# ADC.net
KiCad netlist of a schematic drawn in Altium Designer
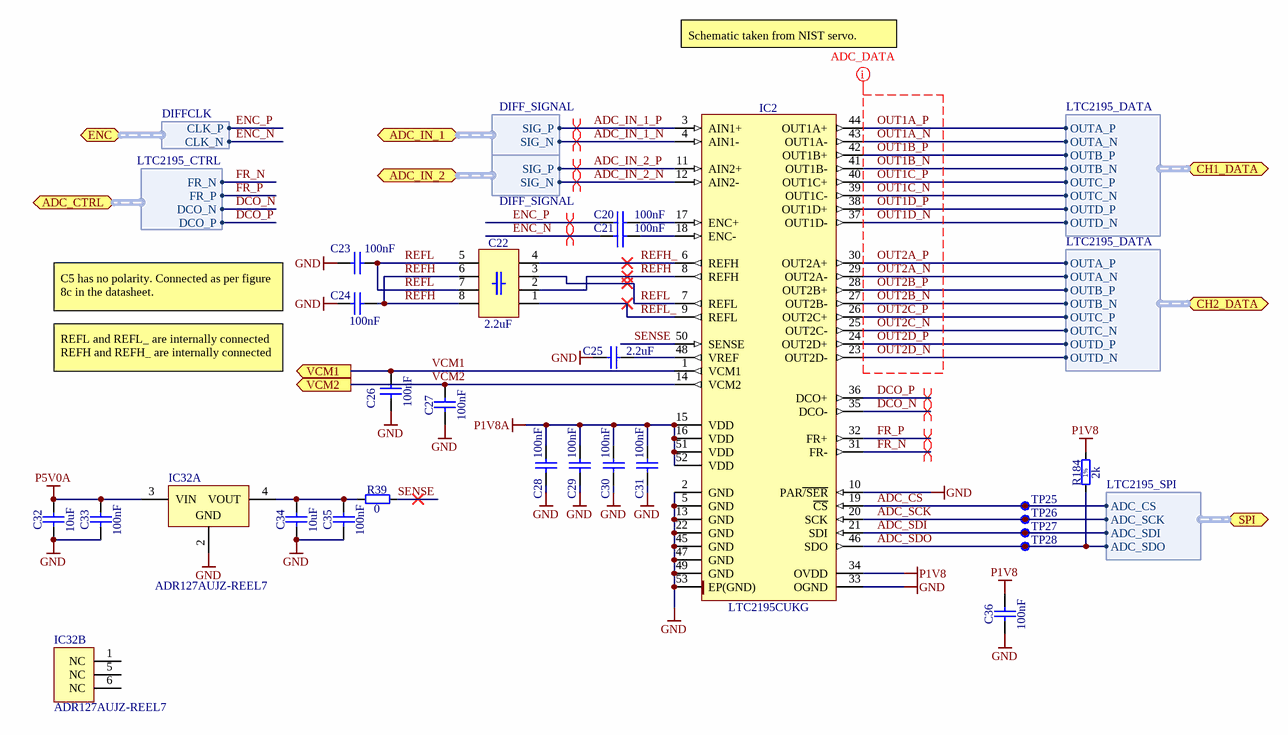
[diagram p0: ADC.SchDoc]

(export (version "E")
  (design (tool "Eeschema 10.0.6"))
  (components
    (comp (ref "C20")
      (value "100nF")
      (footprint "CAPC1005X55N")
      (description "Non-polarised capacitor")
      (fields
        (field (name "PART NUMBER") "CC0402_100NF_16V_10%_X5R")
        (field (name "VOLTAGE") "16V")
        (field (name "AUTHOR") "CERN DEM JLC")
      )
      (libsource (lib "Capacitors") (part "Capacitor - non polarized"))
    )
    (comp (ref "C21")
      (value "100nF")
      (footprint "CAPC1005X55N")
      (description "Non-polarised capacitor")
      (fields
        (field (name "PART NUMBER") "CC0402_100NF_16V_10%_X5R")
        (field (name "VOLTAGE") "16V")
        (field (name "AUTHOR") "CERN DEM JLC")
      )
      (libsource (lib "Capacitors") (part "Capacitor - non polarized"))
    )
    (comp (ref "C22")
      (value "2.2uF")
      (footprint "CAPCAF50P125X200X95-8N")
      (description "8 Terminals Low ESL Chip Multilayer Ceramic Capacitors for General Purpose")
      (fields
        (field (name "PART NUMBER") "CC0508_2.2UF_4V_20%_X7S_MURATA_LLA219C70G225M")
        (field (name "VOLTAGE") "4V")
        (field (name "AUTHOR") "CERN DEM BC")
      )
      (libsource (lib "Capacitors") (part "Capacitor MURATA LLA"))
    )
    (comp (ref "C23")
      (value "100nF")
      (footprint "CAPC1005X55N")
      (description "Non-polarised capacitor")
      (fields
        (field (name "PART NUMBER") "CC0402_100NF_16V_10%_X5R")
        (field (name "VOLTAGE") "16V")
        (field (name "AUTHOR") "CERN DEM JLC")
      )
      (libsource (lib "Capacitors") (part "Capacitor - non polarized"))
    )
    (comp (ref "C24")
      (value "100nF")
      (footprint "CAPC1005X55N")
      (description "Non-polarised capacitor")
      (fields
        (field (name "PART NUMBER") "CC0402_100NF_16V_10%_X5R")
        (field (name "VOLTAGE") "16V")
        (field (name "AUTHOR") "CERN DEM JLC")
      )
      (libsource (lib "Capacitors") (part "Capacitor - non polarized"))
    )
    (comp (ref "C25")
      (value "2.2uF")
      (footprint "CAPC2012X140N")
      (description "Non-polarised capacitor")
      (fields
        (field (name "PART NUMBER") "CC0805_2.2UF_50V_10%_X7R")
        (field (name "VOLTAGE") "50V")
        (field (name "AUTHOR") "CERN DEM JLC")
      )
      (libsource (lib "Capacitors") (part "Capacitor - non polarized"))
    )
    (comp (ref "C26")
      (value "100nF")
      (footprint "CAPC1005X55N")
      (description "Non-polarised capacitor")
      (fields
        (field (name "PART NUMBER") "CC0402_100NF_16V_10%_X5R")
        (field (name "VOLTAGE") "16V")
        (field (name "AUTHOR") "CERN DEM JLC")
      )
      (libsource (lib "Capacitors") (part "Capacitor - non polarized"))
    )
    (comp (ref "C27")
      (value "100nF")
      (footprint "CAPC1005X55N")
      (description "Non-polarised capacitor")
      (fields
        (field (name "PART NUMBER") "CC0402_100NF_16V_10%_X5R")
        (field (name "VOLTAGE") "16V")
        (field (name "AUTHOR") "CERN DEM JLC")
      )
      (libsource (lib "Capacitors") (part "Capacitor - non polarized"))
    )
    (comp (ref "C28")
      (value "100nF")
      (footprint "CAPC1005X55N")
      (description "Non-polarised capacitor")
      (fields
        (field (name "PART NUMBER") "CC0402_100NF_16V_10%_X5R")
        (field (name "VOLTAGE") "16V")
        (field (name "AUTHOR") "CERN DEM JLC")
      )
      (libsource (lib "Capacitors") (part "Capacitor - non polarized"))
    )
    (comp (ref "C29")
      (value "100nF")
      (footprint "CAPC1005X55N")
      (description "Non-polarised capacitor")
      (fields
        (field (name "PART NUMBER") "CC0402_100NF_16V_10%_X5R")
        (field (name "VOLTAGE") "16V")
        (field (name "AUTHOR") "CERN DEM JLC")
      )
      (libsource (lib "Capacitors") (part "Capacitor - non polarized"))
    )
    (comp (ref "C30")
      (value "100nF")
      (footprint "CAPC1005X55N")
      (description "Non-polarised capacitor")
      (fields
        (field (name "PART NUMBER") "CC0402_100NF_16V_10%_X5R")
        (field (name "VOLTAGE") "16V")
        (field (name "AUTHOR") "CERN DEM JLC")
      )
      (libsource (lib "Capacitors") (part "Capacitor - non polarized"))
    )
    (comp (ref "C31")
      (value "100nF")
      (footprint "CAPC1005X55N")
      (description "Non-polarised capacitor")
      (fields
        (field (name "PART NUMBER") "CC0402_100NF_16V_10%_X5R")
        (field (name "VOLTAGE") "16V")
        (field (name "AUTHOR") "CERN DEM JLC")
      )
      (libsource (lib "Capacitors") (part "Capacitor - non polarized"))
    )
    (comp (ref "C32")
      (value "10uF")
      (footprint "CAPC1608X80N")
      (description "Non-polarised capacitor")
      (fields
        (field (name "PART NUMBER") "CC0603_10UF_10V_10%_X5R")
        (field (name "VOLTAGE") "10V")
        (field (name "AUTHOR") "CERN DEM JLC")
      )
      (libsource (lib "Capacitors") (part "Capacitor - non polarized"))
    )
    (comp (ref "C33")
      (value "100nF")
      (footprint "CAPC1005X55N")
      (description "Non-polarised capacitor")
      (fields
        (field (name "PART NUMBER") "CC0402_100NF_16V_10%_X5R")
        (field (name "VOLTAGE") "16V")
        (field (name "AUTHOR") "CERN DEM JLC")
      )
      (libsource (lib "Capacitors") (part "Capacitor - non polarized"))
    )
    (comp (ref "C34")
      (value "10uF")
      (footprint "CAPC1608X80N")
      (description "Non-polarised capacitor")
      (fields
        (field (name "PART NUMBER") "CC0603_10UF_10V_10%_X5R")
        (field (name "VOLTAGE") "10V")
        (field (name "AUTHOR") "CERN DEM JLC")
      )
      (libsource (lib "Capacitors") (part "Capacitor - non polarized"))
    )
    (comp (ref "C35")
      (value "100nF")
      (footprint "CAPC1005X55N")
      (description "Non-polarised capacitor")
      (fields
        (field (name "PART NUMBER") "CC0402_100NF_16V_10%_X5R")
        (field (name "VOLTAGE") "16V")
        (field (name "AUTHOR") "CERN DEM JLC")
      )
      (libsource (lib "Capacitors") (part "Capacitor - non polarized"))
    )
    (comp (ref "C36")
      (value "100nF")
      (footprint "CAPC1005X55N")
      (description "Non-polarised capacitor")
      (fields
        (field (name "PART NUMBER") "CC0402_100NF_16V_10%_X5R")
        (field (name "VOLTAGE") "16V")
        (field (name "AUTHOR") "CERN DEM JLC")
      )
      (libsource (lib "Capacitors") (part "Capacitor - non polarized"))
    )
    (comp (ref "IC2")
      (value "LTC2195CUKG")
      (footprint "QFN50P700X800X80-53N-R655X550")
      (description "16-Bit, 125Msps Low Power Dual ADCs")
      (fields (field (name "MANUFACTURER") "ANALOG DEVICES") (field (name "AUTHOR") "CERN DEM BC"))
      (libsource (lib "ICs And Semiconductors") (part "LTC2195"))
    )
    (comp (ref "IC32")
      (value "ADR127AUJZ-REEL7")
      (footprint "ADI-UJ-6_M")
      (fields (field (name "MANUFACTURER") "Analog Devices"))
      (libsource (lib "Altium Content Vault") (part "ADI-ADR12X-UJ-6"))
    )
    (comp (ref "R39")
      (value "0")
      (footprint "RESC1005X40N")
      (description "Resistor")
      (fields
        (field (name "PART NUMBER") "R0402_0R_JUMPER")
        (field (name "MANUFACTURER") "GENERIC")
        (field (name "AUTHOR") "CERN DEM JLC")
      )
      (libsource (lib "Resistors") (part "Resistor"))
    )
    (comp (ref "R184")
      (value "2k")
      (footprint "RESC1005X40N")
      (description "Resistor - 1%")
      (fields
        (field (name "PART NUMBER") "R0402_2K_1%_0.0625W_100PPM")
        (field (name "MANUFACTURER") "GENERIC")
        (field (name "AUTHOR") "CERN DEM JLC")
      )
      (libsource (lib "Resistors") (part "Resistor - 1%"))
    )
    (comp (ref "TP25")
      (value "SMD Pad")
      (footprint "C100")
      (description "Through Hole Pad")
      (fields (field (name "PART NUMBER") "SMD_PAD_D1MM") (field (name "AUTHOR") "CERN DEM JLC"))
      (libsource (lib "Eletro-mechanical") (part "Single SMD Pad (Round)"))
    )
    (comp (ref "TP26")
      (value "SMD Pad")
      (footprint "C100")
      (description "Through Hole Pad")
      (fields (field (name "PART NUMBER") "SMD_PAD_D1MM") (field (name "AUTHOR") "CERN DEM JLC"))
      (libsource (lib "Eletro-mechanical") (part "Single SMD Pad (Round)"))
    )
    (comp (ref "TP27")
      (value "SMD Pad")
      (footprint "C100")
      (description "Through Hole Pad")
      (fields (field (name "PART NUMBER") "SMD_PAD_D1MM") (field (name "AUTHOR") "CERN DEM JLC"))
      (libsource (lib "Eletro-mechanical") (part "Single SMD Pad (Round)"))
    )
    (comp (ref "TP28")
      (value "SMD Pad")
      (footprint "C100")
      (description "Through Hole Pad")
      (fields (field (name "PART NUMBER") "SMD_PAD_D1MM") (field (name "AUTHOR") "CERN DEM JLC"))
      (libsource (lib "Eletro-mechanical") (part "Single SMD Pad (Round)"))
    )
  )
  (nets
    (net (code "6") (name "/ADC_CS") (class "Default")
      (node (ref "IC2") (pin "19") (pinfunction "CS_19") (pintype "input"))
      (node (ref "TP25") (pin "1") (pinfunction "1_1") (pintype "bidirectional"))
    )
    (net (code "7") (name "/ADC_IN_1_N") (class "Default")
      (node (ref "IC2") (pin "4") (pinfunction "AIN1-_4") (pintype "input"))
    )
    (net (code "8") (name "/ADC_IN_1_P") (class "Default")
      (node (ref "IC2") (pin "3") (pinfunction "AIN1+_3") (pintype "input"))
    )
    (net (code "9") (name "/ADC_IN_2_N") (class "Default")
      (node (ref "IC2") (pin "12") (pinfunction "AIN2-_12") (pintype "input"))
    )
    (net (code "10") (name "/ADC_IN_2_P") (class "Default")
      (node (ref "IC2") (pin "11") (pinfunction "AIN2+_11") (pintype "input"))
    )
    (net (code "11") (name "/ADC_SCK") (class "Default")
      (node (ref "IC2") (pin "20") (pinfunction "SCK_20") (pintype "input"))
      (node (ref "TP26") (pin "1") (pinfunction "1_1") (pintype "bidirectional"))
    )
    (net (code "12") (name "/ADC_SDI") (class "Default")
      (node (ref "IC2") (pin "21") (pinfunction "SDI_21") (pintype "input"))
      (node (ref "TP27") (pin "1") (pinfunction "1_1") (pintype "bidirectional"))
    )
    (net (code "13") (name "/ADC_SDO") (class "Default")
      (node (ref "IC2") (pin "46") (pinfunction "SDO_46") (pintype "output"))
      (node (ref "R184") (pin "1") (pinfunction "1_1") (pintype "passive"))
      (node (ref "TP28") (pin "1") (pinfunction "1_1") (pintype "bidirectional"))
    )
    (net (code "14") (name "/DCO_N") (class "Default")
      (node (ref "IC2") (pin "35") (pinfunction "DCO-_35") (pintype "output"))
    )
    (net (code "15") (name "/DCO_P") (class "Default")
      (node (ref "IC2") (pin "36") (pinfunction "DCO+_36") (pintype "output"))
    )
    (net (code "16") (name "/ENC_N") (class "Default")
      (node (ref "C21") (pin "2") (pinfunction "2_2") (pintype "passive"))
    )
    (net (code "17") (name "/ENC_P") (class "Default")
      (node (ref "C20") (pin "2") (pinfunction "2_2") (pintype "passive"))
    )
    (net (code "18") (name "/FR_N") (class "Default")
      (node (ref "IC2") (pin "31") (pinfunction "FR-_31") (pintype "output"))
    )
    (net (code "19") (name "/FR_P") (class "Default")
      (node (ref "IC2") (pin "32") (pinfunction "FR+_32") (pintype "output"))
    )
    (net (code "20") (name "/OUT1A_N") (class "Default")
      (node (ref "IC2") (pin "43") (pinfunction "OUT1A-_43") (pintype "output"))
    )
    (net (code "21") (name "/OUT1A_P") (class "Default")
      (node (ref "IC2") (pin "44") (pinfunction "OUT1A+_44") (pintype "output"))
    )
    (net (code "22") (name "/OUT1B_N") (class "Default")
      (node (ref "IC2") (pin "41") (pinfunction "OUT1B-_41") (pintype "output"))
    )
    (net (code "23") (name "/OUT1B_P") (class "Default")
      (node (ref "IC2") (pin "42") (pinfunction "OUT1B+_42") (pintype "output"))
    )
    (net (code "24") (name "/OUT1C_N") (class "Default")
      (node (ref "IC2") (pin "39") (pinfunction "OUT1C-_39") (pintype "output"))
    )
    (net (code "25") (name "/OUT1C_P") (class "Default")
      (node (ref "IC2") (pin "40") (pinfunction "OUT1C+_40") (pintype "output"))
    )
    (net (code "26") (name "/OUT1D_N") (class "Default")
      (node (ref "IC2") (pin "37") (pinfunction "OUT1D-_37") (pintype "output"))
    )
    (net (code "27") (name "/OUT1D_P") (class "Default")
      (node (ref "IC2") (pin "38") (pinfunction "OUT1D+_38") (pintype "output"))
    )
    (net (code "28") (name "/OUT2A_N") (class "Default")
      (node (ref "IC2") (pin "29") (pinfunction "OUT2A-_29") (pintype "output"))
    )
    (net (code "29") (name "/OUT2A_P") (class "Default")
      (node (ref "IC2") (pin "30") (pinfunction "OUT2A+_30") (pintype "output"))
    )
    (net (code "30") (name "/OUT2B_N") (class "Default")
      (node (ref "IC2") (pin "27") (pinfunction "OUT2B-_27") (pintype "output"))
    )
    (net (code "31") (name "/OUT2B_P") (class "Default")
      (node (ref "IC2") (pin "28") (pinfunction "OUT2B+_28") (pintype "output"))
    )
    (net (code "32") (name "/OUT2C_N") (class "Default")
      (node (ref "IC2") (pin "25") (pinfunction "OUT2C-_25") (pintype "output"))
    )
    (net (code "33") (name "/OUT2C_P") (class "Default")
      (node (ref "IC2") (pin "26") (pinfunction "OUT2C+_26") (pintype "output"))
    )
    (net (code "34") (name "/OUT2D_N") (class "Default")
      (node (ref "IC2") (pin "23") (pinfunction "OUT2D-_23") (pintype "output"))
    )
    (net (code "35") (name "/OUT2D_P") (class "Default")
      (node (ref "IC2") (pin "24") (pinfunction "OUT2D+_24") (pintype "output"))
    )
    (net (code "36") (name "/REFH") (class "Default")
      (node (ref "C22") (pin "2") (pinfunction "2_2") (pintype "passive"))
      (node (ref "C22") (pin "6") (pinfunction "6_6") (pintype "passive"))
      (node (ref "C22") (pin "8") (pinfunction "8_8") (pintype "passive"))
      (node (ref "C24") (pin "1") (pinfunction "1_1") (pintype "passive"))
      (node (ref "IC2") (pin "8") (pinfunction "REFH_8") (pintype "output"))
    )
    (net (code "37") (name "/REFH_") (class "Default")
      (node (ref "C22") (pin "4") (pinfunction "4_4") (pintype "passive"))
      (node (ref "IC2") (pin "6") (pinfunction "REFH_6") (pintype "output"))
    )
    (net (code "38") (name "/REFL") (class "Default")
      (node (ref "C22") (pin "3") (pinfunction "3_3") (pintype "passive"))
      (node (ref "C22") (pin "5") (pinfunction "5_5") (pintype "passive"))
      (node (ref "C22") (pin "7") (pinfunction "7_7") (pintype "passive"))
      (node (ref "C23") (pin "1") (pinfunction "1_1") (pintype "passive"))
      (node (ref "IC2") (pin "7") (pinfunction "REFL_7") (pintype "output"))
    )
    (net (code "39") (name "/REFL_") (class "Default")
      (node (ref "C22") (pin "1") (pinfunction "1_1") (pintype "passive"))
      (node (ref "IC2") (pin "9") (pinfunction "REFL_9") (pintype "output"))
    )
    (net (code "40") (name "/SENSE") (class "Default")
      (node (ref "IC2") (pin "50") (pinfunction "SENSE_50") (pintype "input"))
      (node (ref "R39") (pin "2") (pinfunction "2_2") (pintype "passive"))
    )
    (net (code "41") (name "/VCM1") (class "Default")
      (node (ref "C26") (pin "2") (pinfunction "2_2") (pintype "passive"))
      (node (ref "IC2") (pin "1") (pinfunction "VCM1_1") (pintype "output"))
    )
    (net (code "42") (name "/VCM2") (class "Default")
      (node (ref "C27") (pin "2") (pinfunction "2_2") (pintype "passive"))
      (node (ref "IC2") (pin "14") (pinfunction "VCM2_14") (pintype "output"))
    )
    (net (code "48") (name "GND") (class "Default")
      (node (ref "C23") (pin "2") (pinfunction "2_2") (pintype "passive"))
      (node (ref "C24") (pin "2") (pinfunction "2_2") (pintype "passive"))
      (node (ref "C25") (pin "1") (pinfunction "1_1") (pintype "passive"))
      (node (ref "C26") (pin "1") (pinfunction "1_1") (pintype "passive"))
      (node (ref "C27") (pin "1") (pinfunction "1_1") (pintype "passive"))
      (node (ref "C28") (pin "2") (pinfunction "2_2") (pintype "passive"))
      (node (ref "C29") (pin "2") (pinfunction "2_2") (pintype "passive"))
      (node (ref "C30") (pin "2") (pinfunction "2_2") (pintype "passive"))
      (node (ref "C31") (pin "2") (pinfunction "2_2") (pintype "passive"))
      (node (ref "C32") (pin "1") (pinfunction "1_1") (pintype "passive"))
      (node (ref "C33") (pin "1") (pinfunction "1_1") (pintype "passive"))
      (node (ref "C34") (pin "1") (pinfunction "1_1") (pintype "passive"))
      (node (ref "C35") (pin "1") (pinfunction "1_1") (pintype "passive"))
      (node (ref "C36") (pin "1") (pinfunction "1_1") (pintype "passive"))
      (node (ref "IC2") (pin "10") (pinfunction "PAR~{/SER}_10") (pintype "input"))
      (node (ref "IC2") (pin "13") (pinfunction "GND_13") (pintype "power_in"))
      (node (ref "IC2") (pin "2") (pinfunction "GND_2") (pintype "power_in"))
      (node (ref "IC2") (pin "22") (pinfunction "GND_22") (pintype "power_in"))
      (node (ref "IC2") (pin "33") (pinfunction "OGND_33") (pintype "power_in"))
      (node (ref "IC2") (pin "45") (pinfunction "GND_45") (pintype "power_in"))
      (node (ref "IC2") (pin "47") (pinfunction "GND_47") (pintype "power_in"))
      (node (ref "IC2") (pin "49") (pinfunction "GND_49") (pintype "power_in"))
      (node (ref "IC2") (pin "5") (pinfunction "GND_5") (pintype "power_in"))
      (node (ref "IC2") (pin "53") (pinfunction "EP(GND)_53") (pintype "power_in"))
      (node (ref "IC32") (pin "2") (pinfunction "GND_2") (pintype "power_in"))
    )
    (net (code "49") (name "Net-(IC2-ENC+)") (class "Default")
      (node (ref "C20") (pin "1") (pinfunction "1_1") (pintype "passive"))
      (node (ref "IC2") (pin "17") (pinfunction "ENC+_17") (pintype "input"))
    )
    (net (code "50") (name "Net-(IC2-ENC-)") (class "Default")
      (node (ref "C21") (pin "1") (pinfunction "1_1") (pintype "passive"))
      (node (ref "IC2") (pin "18") (pinfunction "ENC-_18") (pintype "input"))
    )
    (net (code "51") (name "Net-(IC2-VREF)") (class "Default")
      (node (ref "C25") (pin "2") (pinfunction "2_2") (pintype "passive"))
      (node (ref "IC2") (pin "48") (pinfunction "VREF_48") (pintype "output"))
    )
    (net (code "52") (name "Net-(IC32A-VOUT)") (class "Default")
      (node (ref "C34") (pin "2") (pinfunction "2_2") (pintype "passive"))
      (node (ref "C35") (pin "2") (pinfunction "2_2") (pintype "passive"))
      (node (ref "IC32") (pin "4") (pinfunction "VOUT_4") (pintype "power_in"))
      (node (ref "R39") (pin "1") (pinfunction "1_1") (pintype "passive"))
    )
    (net (code "53") (name "P1V8") (class "Default")
      (node (ref "C36") (pin "2") (pinfunction "2_2") (pintype "passive"))
      (node (ref "IC2") (pin "34") (pinfunction "OVDD_34") (pintype "power_in"))
      (node (ref "R184") (pin "2") (pinfunction "2_2") (pintype "passive"))
    )
    (net (code "54") (name "P1V8A") (class "Default")
      (node (ref "C28") (pin "1") (pinfunction "1_1") (pintype "passive"))
      (node (ref "C29") (pin "1") (pinfunction "1_1") (pintype "passive"))
      (node (ref "C30") (pin "1") (pinfunction "1_1") (pintype "passive"))
      (node (ref "C31") (pin "1") (pinfunction "1_1") (pintype "passive"))
      (node (ref "IC2") (pin "15") (pinfunction "VDD_15") (pintype "power_in"))
      (node (ref "IC2") (pin "16") (pinfunction "VDD_16") (pintype "power_in"))
      (node (ref "IC2") (pin "51") (pinfunction "VDD_51") (pintype "power_in"))
      (node (ref "IC2") (pin "52") (pinfunction "VDD_52") (pintype "power_in"))
    )
    (net (code "55") (name "P5V0A") (class "Default")
      (node (ref "C32") (pin "2") (pinfunction "2_2") (pintype "passive"))
      (node (ref "C33") (pin "2") (pinfunction "2_2") (pintype "passive"))
      (node (ref "IC32") (pin "3") (pinfunction "VIN_3") (pintype "power_in"))
    )
    (net (code "56") (name "unconnected-(IC32B-NC-Pad1)") (class "Default")
      (node (ref "IC32") (pin "1") (pinfunction "NC_1") (pintype "passive"))
    )
    (net (code "57") (name "unconnected-(IC32B-NC-Pad5)") (class "Default")
      (node (ref "IC32") (pin "5") (pinfunction "NC_5") (pintype "passive"))
    )
    (net (code "58") (name "unconnected-(IC32B-NC-Pad6)") (class "Default")
      (node (ref "IC32") (pin "6") (pinfunction "NC_6") (pintype "passive"))
    )
  )
)
